# Sheet1.net
KiCad netlist of a schematic drawn in Altium Designer
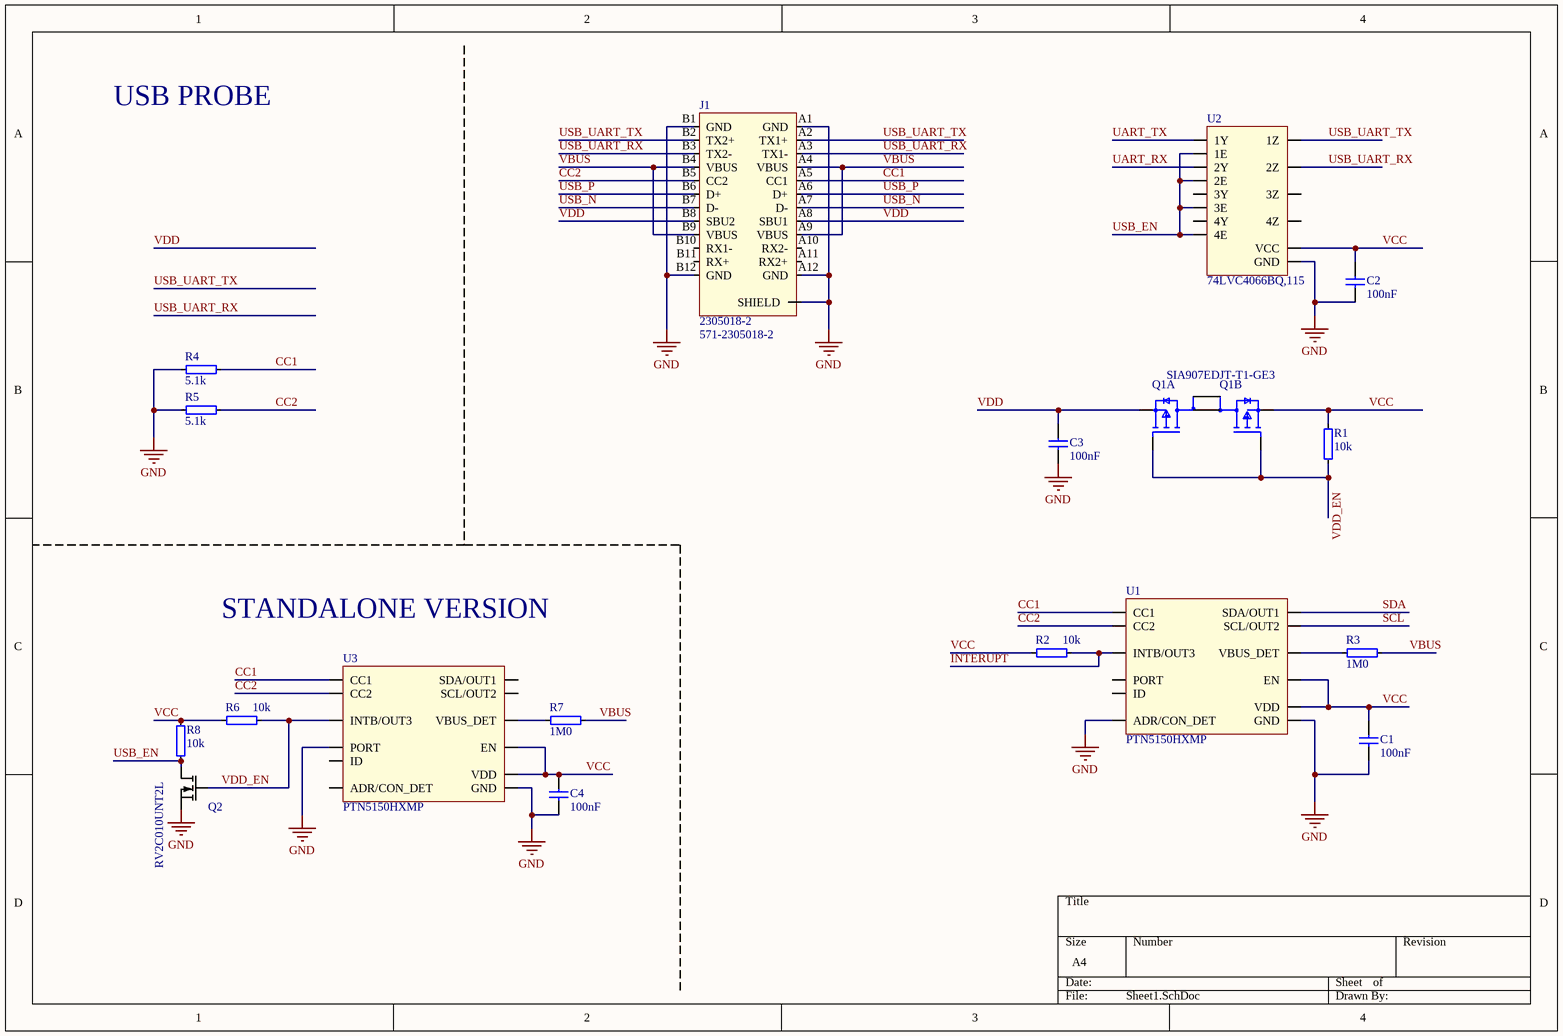
[diagram p0: Sheet1.SchDoc]

(export (version "E")
  (design (tool "Eeschema 10.0.6"))
  (components
    (comp (ref "C1")
      (value "100nF")
      (footprint "CAPC0603X03L_C")
      (description "Capacitor, X5R, ±10%")
      (fields (field (name "PART NUMBER") "C0201-100n") (field (name "MANUFACTURER") "N.A."))
      (libsource (lib "main") (part "C0201-100n"))
    )
    (comp (ref "C2")
      (value "100nF")
      (footprint "CAPC0603X03L_C")
      (description "Capacitor, X5R, ±10%")
      (fields (field (name "PART NUMBER") "C0201-100n") (field (name "MANUFACTURER") "N.A."))
      (libsource (lib "main") (part "C0201-100n"))
    )
    (comp (ref "C3")
      (value "100nF")
      (footprint "CAPC0603X03L_C")
      (description "Capacitor, X5R, ±10%")
      (fields (field (name "PART NUMBER") "C0201-100n") (field (name "MANUFACTURER") "N.A."))
      (libsource (lib "main") (part "C0201-100n"))
    )
    (comp (ref "C4")
      (value "100nF")
      (footprint "CAPC0603X03L_C")
      (description "Capacitor, X5R, ±10%")
      (fields (field (name "PART NUMBER") "C0201-100n") (field (name "MANUFACTURER") "N.A."))
      (libsource (lib "main") (part "C0201-100n"))
    )
    (comp (ref "J1")
      (value "2305018-2")
      (footprint "2305018-2")
      (description "Usb 3.1 Type C, 10GBPS, Receptacle, Rigusb Connectors Usb Type C, Rec IPX8 on Board Dual SMT")
      (fields
        (field (name "MANUFACTURER") "TE Connectivity AMP")
        (field (name "SUPPLIER PART NUMBER 1") "571-2305018-2")
      )
      (libsource (lib "Schlib1") (part "2305018-2"))
    )
    (comp (ref "Q1")
      (value "SIA907EDJT-T1-GE3")
      (footprint "FP-C-07431-DUAL-MFG")
      (description "SiA907EDJT Series Dual P Channel 20 V 0.057 Ohm 7.8 W Mosfet - PowerPAK SC-70-6L")
      (fields (field (name "MANUFACTURER") "Vishay Siliconix"))
      (libsource (lib "Schlib1") (part "SIA907EDJT-T1-GE3"))
    )
    (comp (ref "Q2")
      (value "RV2C010UNT2L")
      (footprint "DFN65P100X40-3L")
      (description "MOSFET Transistor, N Channel, 1 A, 20 V, 0.34 ohm, 4.5 V, 1 V RoHS Compliant: Yes")
      (fields (field (name "MANUFACTURER") "Rohm"))
      (libsource (lib "Schlib1") (part "RV2C010UNT2L"))
    )
    (comp (ref "R1")
      (value "10k")
      (footprint "RESC0603X03L_C")
      (description "Resistor, ±1%, 0.05W")
      (fields (field (name "PART NUMBER") "R0201-10k") (field (name "MANUFACTURER") "N.A."))
      (libsource (lib "main") (part "R0201-10k"))
    )
    (comp (ref "R2")
      (value "10k")
      (footprint "RESC0603X03L_C")
      (description "Resistor, ±1%, 0.05W")
      (fields (field (name "PART NUMBER") "R0201-10k") (field (name "MANUFACTURER") "N.A."))
      (libsource (lib "main") (part "R0201-10k"))
    )
    (comp (ref "R3")
      (value "1M0")
      (footprint "RESC0603X03L_C")
      (description "Resistor, ±1%, 0.05W")
      (fields (field (name "PART NUMBER") "R0201-1M0") (field (name "MANUFACTURER") "N.A."))
      (libsource (lib "main") (part "R0201-1M0"))
    )
    (comp (ref "R4")
      (value "5.1k")
      (footprint "RESC0603X03L_C")
      (description "Resistor, ±1%, 0.05W")
      (fields (field (name "PART NUMBER") "R0201-4k7") (field (name "MANUFACTURER") "N.A."))
      (libsource (lib "main") (part "R0201-4k7"))
    )
    (comp (ref "R5")
      (value "5.1k")
      (footprint "RESC0603X03L_C")
      (description "Resistor, ±1%, 0.05W")
      (fields (field (name "PART NUMBER") "R0201-4k7") (field (name "MANUFACTURER") "N.A."))
      (libsource (lib "main") (part "R0201-4k7"))
    )
    (comp (ref "R6")
      (value "10k")
      (footprint "RESC0603X03L_C")
      (description "Resistor, ±1%, 0.05W")
      (fields (field (name "PART NUMBER") "R0201-10k") (field (name "MANUFACTURER") "N.A."))
      (libsource (lib "main") (part "R0201-10k"))
    )
    (comp (ref "R7")
      (value "1M0")
      (footprint "RESC0603X03L_C")
      (description "Resistor, ±1%, 0.05W")
      (fields (field (name "PART NUMBER") "R0201-1M0") (field (name "MANUFACTURER") "N.A."))
      (libsource (lib "main") (part "R0201-1M0"))
    )
    (comp (ref "R8")
      (value "10k")
      (footprint "RESC0603X03L_C")
      (description "Resistor, ±1%, 0.05W")
      (fields (field (name "PART NUMBER") "R0201-10k") (field (name "MANUFACTURER") "N.A."))
      (libsource (lib "main") (part "R0201-10k"))
    )
    (comp (ref "U1")
      (value "PTN5150HXMP")
      (footprint "PTN5150HXMP")
      (description "Usb Interface IC PTN5150HX/X2QFN12/REEL 13\" Q2/")
      (fields (field (name "MANUFACTURER") "NXP Semiconductors"))
      (libsource (lib "Schlib1") (part "PTN5150HXMP"))
    )
    (comp (ref "U2")
      (value "74LVC4066BQ,115")
      (footprint "74LVC4066BQ,115")
      (description "74LVC Series 5.5 V Quad Bilateral Switch - DHVQFN-14")
      (fields (field (name "MANUFACTURER") "Nexperia"))
      (libsource (lib "Schlib1") (part "74LVC4066BQ,115"))
    )
    (comp (ref "U3")
      (value "PTN5150HXMP")
      (footprint "PTN5150HXMP")
      (description "Usb Interface IC PTN5150HX/X2QFN12/REEL 13\" Q2/")
      (fields (field (name "MANUFACTURER") "NXP Semiconductors"))
      (libsource (lib "Schlib1") (part "PTN5150HXMP"))
    )
  )
  (nets
    (net (code "1") (name "/CC1") (class "Default")
      (node (ref "J1") (pin "A5") (pinfunction "CC1_A5") (pintype "passive"))
      (node (ref "R4") (pin "2") (pinfunction "2_2") (pintype "passive"))
      (node (ref "U1") (pin "P1") (pinfunction "CC1_P1") (pintype "passive"))
      (node (ref "U3") (pin "P1") (pinfunction "CC1_P1") (pintype "passive"))
    )
    (net (code "2") (name "/CC2") (class "Default")
      (node (ref "J1") (pin "B5") (pinfunction "CC2_B5") (pintype "passive"))
      (node (ref "R5") (pin "2") (pinfunction "2_2") (pintype "passive"))
      (node (ref "U1") (pin "P2") (pinfunction "CC2_P2") (pintype "passive"))
      (node (ref "U3") (pin "P2") (pinfunction "CC2_P2") (pintype "passive"))
    )
    (net (code "3") (name "/INTERUPT") (class "Default")
      (node (ref "R2") (pin "2") (pinfunction "2_2") (pintype "passive"))
      (node (ref "U1") (pin "P6") (pinfunction "INTB/OUT3_P6") (pintype "passive"))
    )
    (net (code "4") (name "/SCL") (class "Default")
      (node (ref "U1") (pin "P8") (pinfunction "SCL/OUT2_P8") (pintype "passive"))
    )
    (net (code "5") (name "/SDA") (class "Default")
      (node (ref "U1") (pin "P7") (pinfunction "SDA/OUT1_P7") (pintype "passive"))
    )
    (net (code "6") (name "/UART_RX") (class "Default")
      (node (ref "U2") (pin "P4") (pinfunction "2Y_P4") (pintype "passive"))
    )
    (net (code "7") (name "/UART_TX") (class "Default")
      (node (ref "U2") (pin "P1") (pinfunction "1Y_P1") (pintype "passive"))
    )
    (net (code "8") (name "/USB_EN") (class "Default")
      (node (ref "Q2") (pin "3") (pinfunction "D_3") (pintype "passive"))
      (node (ref "R8") (pin "1") (pinfunction "1_1") (pintype "passive"))
      (node (ref "U2") (pin "P12") (pinfunction "4E_P12") (pintype "passive"))
      (node (ref "U2") (pin "P13") (pinfunction "1E_P13") (pintype "passive"))
      (node (ref "U2") (pin "P5") (pinfunction "2E_P5") (pintype "passive"))
      (node (ref "U2") (pin "P6") (pinfunction "3E_P6") (pintype "passive"))
    )
    (net (code "9") (name "/USB_N") (class "Default")
      (node (ref "J1") (pin "A7") (pinfunction "D-_A7") (pintype "passive"))
      (node (ref "J1") (pin "B7") (pinfunction "D-_B7") (pintype "passive"))
    )
    (net (code "10") (name "/USB_P") (class "Default")
      (node (ref "J1") (pin "A6") (pinfunction "D+_A6") (pintype "passive"))
      (node (ref "J1") (pin "B6") (pinfunction "D+_B6") (pintype "passive"))
    )
    (net (code "11") (name "/USB_UART_RX") (class "Default")
      (node (ref "J1") (pin "A3") (pinfunction "TX1-_A3") (pintype "passive"))
      (node (ref "J1") (pin "B3") (pinfunction "TX2-_B3") (pintype "passive"))
      (node (ref "U2") (pin "P3") (pinfunction "2Z_P3") (pintype "passive"))
    )
    (net (code "12") (name "/USB_UART_TX") (class "Default")
      (node (ref "J1") (pin "A2") (pinfunction "TX1+_A2") (pintype "passive"))
      (node (ref "J1") (pin "B2") (pinfunction "TX2+_B2") (pintype "passive"))
      (node (ref "U2") (pin "P2") (pinfunction "1Z_P2") (pintype "passive"))
    )
    (net (code "13") (name "/VBUS") (class "Default")
      (node (ref "J1") (pin "A4") (pinfunction "VBUS_A4") (pintype "passive"))
      (node (ref "J1") (pin "A9") (pinfunction "VBUS_A9") (pintype "passive"))
      (node (ref "J1") (pin "B4") (pinfunction "VBUS_B4") (pintype "passive"))
      (node (ref "J1") (pin "B9") (pinfunction "VBUS_B9") (pintype "passive"))
      (node (ref "R3") (pin "2") (pinfunction "2_2") (pintype "passive"))
      (node (ref "R7") (pin "2") (pinfunction "2_2") (pintype "passive"))
    )
    (net (code "14") (name "/VCC") (class "Default")
      (node (ref "C1") (pin "2") (pinfunction "2_2") (pintype "passive"))
      (node (ref "C2") (pin "2") (pinfunction "2_2") (pintype "passive"))
      (node (ref "C4") (pin "2") (pinfunction "2_2") (pintype "passive"))
      (node (ref "Q1") (pin "4") (pinfunction "S2_4") (pintype "passive"))
      (node (ref "R1") (pin "2") (pinfunction "2_2") (pintype "passive"))
      (node (ref "R2") (pin "1") (pinfunction "1_1") (pintype "passive"))
      (node (ref "R6") (pin "1") (pinfunction "1_1") (pintype "passive"))
      (node (ref "R8") (pin "2") (pinfunction "2_2") (pintype "passive"))
      (node (ref "U1") (pin "P11") (pinfunction "EN_P11") (pintype "passive"))
      (node (ref "U1") (pin "P12") (pinfunction "VDD_P12") (pintype "passive"))
      (node (ref "U2") (pin "P14") (pinfunction "VCC_P14") (pintype "passive"))
      (node (ref "U3") (pin "P11") (pinfunction "EN_P11") (pintype "passive"))
      (node (ref "U3") (pin "P12") (pinfunction "VDD_P12") (pintype "passive"))
    )
    (net (code "15") (name "/VDD") (class "Default")
      (node (ref "C3") (pin "2") (pinfunction "2_2") (pintype "passive"))
      (node (ref "J1") (pin "A8") (pinfunction "SBU1_A8") (pintype "passive"))
      (node (ref "J1") (pin "B8") (pinfunction "SBU2_B8") (pintype "passive"))
      (node (ref "Q1") (pin "1") (pinfunction "S1_1") (pintype "passive"))
    )
    (net (code "16") (name "/VDD_EN") (class "Default")
      (node (ref "Q1") (pin "2") (pinfunction "G1_2") (pintype "passive"))
      (node (ref "Q1") (pin "5") (pinfunction "G2_5") (pintype "passive"))
      (node (ref "Q2") (pin "1") (pinfunction "G_1") (pintype "passive"))
      (node (ref "R1") (pin "1") (pinfunction "1_1") (pintype "passive"))
      (node (ref "R6") (pin "2") (pinfunction "2_2") (pintype "passive"))
      (node (ref "U3") (pin "P6") (pinfunction "INTB/OUT3_P6") (pintype "passive"))
    )
    (net (code "17") (name "GND") (class "Default")
      (node (ref "C1") (pin "1") (pinfunction "1_1") (pintype "passive"))
      (node (ref "C2") (pin "1") (pinfunction "1_1") (pintype "passive"))
      (node (ref "C3") (pin "1") (pinfunction "1_1") (pintype "passive"))
      (node (ref "C4") (pin "1") (pinfunction "1_1") (pintype "passive"))
      (node (ref "J1") (pin "A1") (pinfunction "GND_A1") (pintype "passive"))
      (node (ref "J1") (pin "A12") (pinfunction "GND_A12") (pintype "passive"))
      (node (ref "J1") (pin "B1") (pinfunction "GND_B1") (pintype "passive"))
      (node (ref "J1") (pin "B12") (pinfunction "GND_B12") (pintype "passive"))
      (node (ref "J1") (pin "SH1") (pinfunction "SHIELD_SH1") (pintype "passive"))
      (node (ref "Q2") (pin "2") (pinfunction "S_2") (pintype "passive"))
      (node (ref "R4") (pin "1") (pinfunction "1_1") (pintype "passive"))
      (node (ref "R5") (pin "1") (pinfunction "1_1") (pintype "passive"))
      (node (ref "U1") (pin "P10") (pinfunction "GND_P10") (pintype "passive"))
      (node (ref "U1") (pin "P5") (pinfunction "ADR/CON_DET_P5") (pintype "passive"))
      (node (ref "U2") (pin "P7") (pinfunction "GND_P7") (pintype "passive"))
      (node (ref "U3") (pin "P10") (pinfunction "GND_P10") (pintype "passive"))
      (node (ref "U3") (pin "P3") (pinfunction "PORT_P3") (pintype "passive"))
    )
    (net (code "18") (name "Net-(Q1A-D1-Pad6)") (class "Default")
      (node (ref "Q1") (pin "3") (pinfunction "D2_3") (pintype "passive"))
      (node (ref "Q1") (pin "6") (pinfunction "D1_6") (pintype "passive"))
    )
    (net (code "19") (name "Net-(Q1A-D1-Pad7)") (class "Default")
      (node (ref "Q1") (pin "7") (pinfunction "D1_7") (pintype "passive"))
      (node (ref "Q1") (pin "8") (pinfunction "D2_8") (pintype "passive"))
    )
    (net (code "20") (name "Net-(U1-VBUS_DET)") (class "Default")
      (node (ref "R3") (pin "1") (pinfunction "1_1") (pintype "passive"))
      (node (ref "U1") (pin "P4") (pinfunction "VBUS_DET_P4") (pintype "passive"))
    )
    (net (code "21") (name "Net-(U3-VBUS_DET)") (class "Default")
      (node (ref "R7") (pin "1") (pinfunction "1_1") (pintype "passive"))
      (node (ref "U3") (pin "P4") (pinfunction "VBUS_DET_P4") (pintype "passive"))
    )
    (net (code "22") (name "unconnected-(J1-RX+-PadB11)") (class "Default")
      (node (ref "J1") (pin "B11") (pinfunction "RX+_B11") (pintype "passive"))
    )
    (net (code "23") (name "unconnected-(J1-RX1--PadB10)") (class "Default")
      (node (ref "J1") (pin "B10") (pinfunction "RX1-_B10") (pintype "passive"))
    )
    (net (code "24") (name "unconnected-(J1-RX2+-PadA11)") (class "Default")
      (node (ref "J1") (pin "A11") (pinfunction "RX2+_A11") (pintype "passive"))
    )
    (net (code "25") (name "unconnected-(J1-RX2--PadA10)") (class "Default")
      (node (ref "J1") (pin "A10") (pinfunction "RX2-_A10") (pintype "passive"))
    )
    (net (code "26") (name "unconnected-(U1-ID-PadP9)") (class "Default")
      (node (ref "U1") (pin "P9") (pinfunction "ID_P9") (pintype "passive"))
    )
    (net (code "27") (name "unconnected-(U1-PORT-PadP3)") (class "Default")
      (node (ref "U1") (pin "P3") (pinfunction "PORT_P3") (pintype "passive"))
    )
    (net (code "28") (name "unconnected-(U2-3Y-PadP8)") (class "Default")
      (node (ref "U2") (pin "P8") (pinfunction "3Y_P8") (pintype "passive"))
    )
    (net (code "29") (name "unconnected-(U2-3Z-PadP9)") (class "Default")
      (node (ref "U2") (pin "P9") (pinfunction "3Z_P9") (pintype "passive"))
    )
    (net (code "30") (name "unconnected-(U2-4Y-PadP11)") (class "Default")
      (node (ref "U2") (pin "P11") (pinfunction "4Y_P11") (pintype "passive"))
    )
    (net (code "31") (name "unconnected-(U2-4Z-PadP10)") (class "Default")
      (node (ref "U2") (pin "P10") (pinfunction "4Z_P10") (pintype "passive"))
    )
    (net (code "32") (name "unconnected-(U3-ADR{slash}CON_DET-PadP5)") (class "Default")
      (node (ref "U3") (pin "P5") (pinfunction "ADR/CON_DET_P5") (pintype "passive"))
    )
    (net (code "33") (name "unconnected-(U3-ID-PadP9)") (class "Default")
      (node (ref "U3") (pin "P9") (pinfunction "ID_P9") (pintype "passive"))
    )
    (net (code "34") (name "unconnected-(U3-SCL{slash}OUT2-PadP8)") (class "Default")
      (node (ref "U3") (pin "P8") (pinfunction "SCL/OUT2_P8") (pintype "passive"))
    )
    (net (code "35") (name "unconnected-(U3-SDA{slash}OUT1-PadP7)") (class "Default")
      (node (ref "U3") (pin "P7") (pinfunction "SDA/OUT1_P7") (pintype "passive"))
    )
  )
)
